# Power_IN.net
KiCad netlist of a schematic drawn in Altium Designer
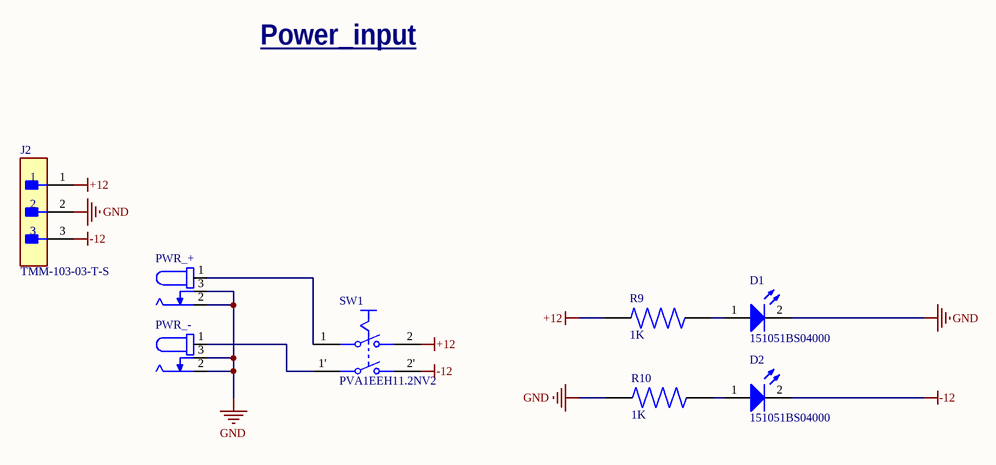
[diagram p0: Power_IN.SchDoc]

(export (version "E")
  (design (tool "Eeschema 10.0.6"))
  (components
    (comp (ref "D1")
      (value "151051BS04000")
      (footprint "WL-TMRC_D5.9H8.7")
      (libsource (lib "Altium Content Vault") (part "LED_Blue_1A-2K"))
    )
    (comp (ref "D2")
      (value "151051BS04000")
      (footprint "WL-TMRC_D5.9H8.7")
      (libsource (lib "Altium Content Vault") (part "LED_Blue_1A-2K"))
    )
    (comp (ref "J2")
      (value "TMM-103-03-T-S")
      (footprint "FP-TMM-103-03-T-S-MFG")
      (description "CONN HEADER VERT 3POS 2MM")
      (libsource (lib "Altium Content Vault") (part "0d3f023dd272f625e17a2be33dea85f"))
    )
    (comp (ref "PWR_+")
      (value "Component_2")
      (footprint "694106301002")
      (libsource (lib "Integrated_Library1") (part "Component_2"))
    )
    (comp (ref "PWR_-")
      (value "Component_2")
      (footprint "694106301002")
      (libsource (lib "Integrated_Library1") (part "Component_2"))
    )
    (comp (ref "R9")
      (value "1K")
      (footprint "RESAD1100W55L680D260")
      (description "1.07 kOhms Â±1% 0.25W, 1/4W Through Hole Resistor Axial - Metal Film")
      (fields (field (name "MF") "Yageo") (field (name "MP") "MFR-25FBF52-1K"))
      (libsource (lib "MFR-25FBF52-1K") (part "MFR-25FBF52-1K"))
    )
    (comp (ref "R10")
      (value "1K")
      (footprint "RESAD1100W55L680D260")
      (description "1.07 kOhms Â±1% 0.25W, 1/4W Through Hole Resistor Axial - Metal Film")
      (fields (field (name "MF") "Yageo") (field (name "MP") "MFR-25FBF52-1K"))
      (libsource (lib "MFR-25FBF52-1K") (part "MFR-25FBF52-1K"))
    )
    (comp (ref "SW1")
      (value "PVA1EEH11.2NV2")
      (footprint "FP-PVA1EEH11_2NV2-MFG")
      (description "SWITCH PUSH DPST 0.1A 32V")
      (libsource (lib "Altium Content Vault") (part "0a7b0f685d7af6e0316c3509192f32d"))
    )
  )
  (nets
    (net (code "1") (name "+12") (class "Default")
      (node (ref "J2") (pin "1") (pinfunction "1_1") (pintype "passive"))
      (node (ref "R9") (pin "1") (pinfunction "1_1") (pintype "passive"))
      (node (ref "SW1") (pin "2") (pinfunction "2_2") (pintype "passive"))
    )
    (net (code "2") (name "-12") (class "Default")
      (node (ref "D2") (pin "2") (pinfunction "K_2") (pintype "passive"))
      (node (ref "J2") (pin "3") (pinfunction "3_3") (pintype "passive"))
      (node (ref "SW1") (pin "2'") (pinfunction "2'_2'") (pintype "passive"))
    )
    (net (code "3") (name "GND") (class "Default")
      (node (ref "D1") (pin "2") (pinfunction "K_2") (pintype "passive"))
      (node (ref "J2") (pin "2") (pinfunction "2_2") (pintype "passive"))
      (node (ref "PWR_+") (pin "2") (pinfunction "2_2") (pintype "passive"))
      (node (ref "PWR_+") (pin "3") (pinfunction "3_3") (pintype "passive"))
      (node (ref "PWR_-") (pin "2") (pinfunction "2_2") (pintype "passive"))
      (node (ref "PWR_-") (pin "3") (pinfunction "3_3") (pintype "passive"))
      (node (ref "R10") (pin "1") (pinfunction "1_1") (pintype "passive"))
    )
    (net (code "4") (name "Net-(D1-A)") (class "Default")
      (node (ref "D1") (pin "1") (pinfunction "A_1") (pintype "passive"))
      (node (ref "R9") (pin "2") (pinfunction "2_2") (pintype "passive"))
    )
    (net (code "5") (name "Net-(D2-A)") (class "Default")
      (node (ref "D2") (pin "1") (pinfunction "A_1") (pintype "passive"))
      (node (ref "R10") (pin "2") (pinfunction "2_2") (pintype "passive"))
    )
    (net (code "6") (name "Net-(PWR_+-Pad1)") (class "Default")
      (node (ref "PWR_+") (pin "1") (pinfunction "1_1") (pintype "passive"))
      (node (ref "SW1") (pin "1") (pinfunction "1_1") (pintype "passive"))
    )
    (net (code "7") (name "Net-(PWR_--Pad1)") (class "Default")
      (node (ref "PWR_-") (pin "1") (pinfunction "1_1") (pintype "passive"))
      (node (ref "SW1") (pin "1'") (pinfunction "1'_1'") (pintype "passive"))
    )
  )
)
